# ir_receiver.net
KiCad netlist of a schematic drawn in EAGLE
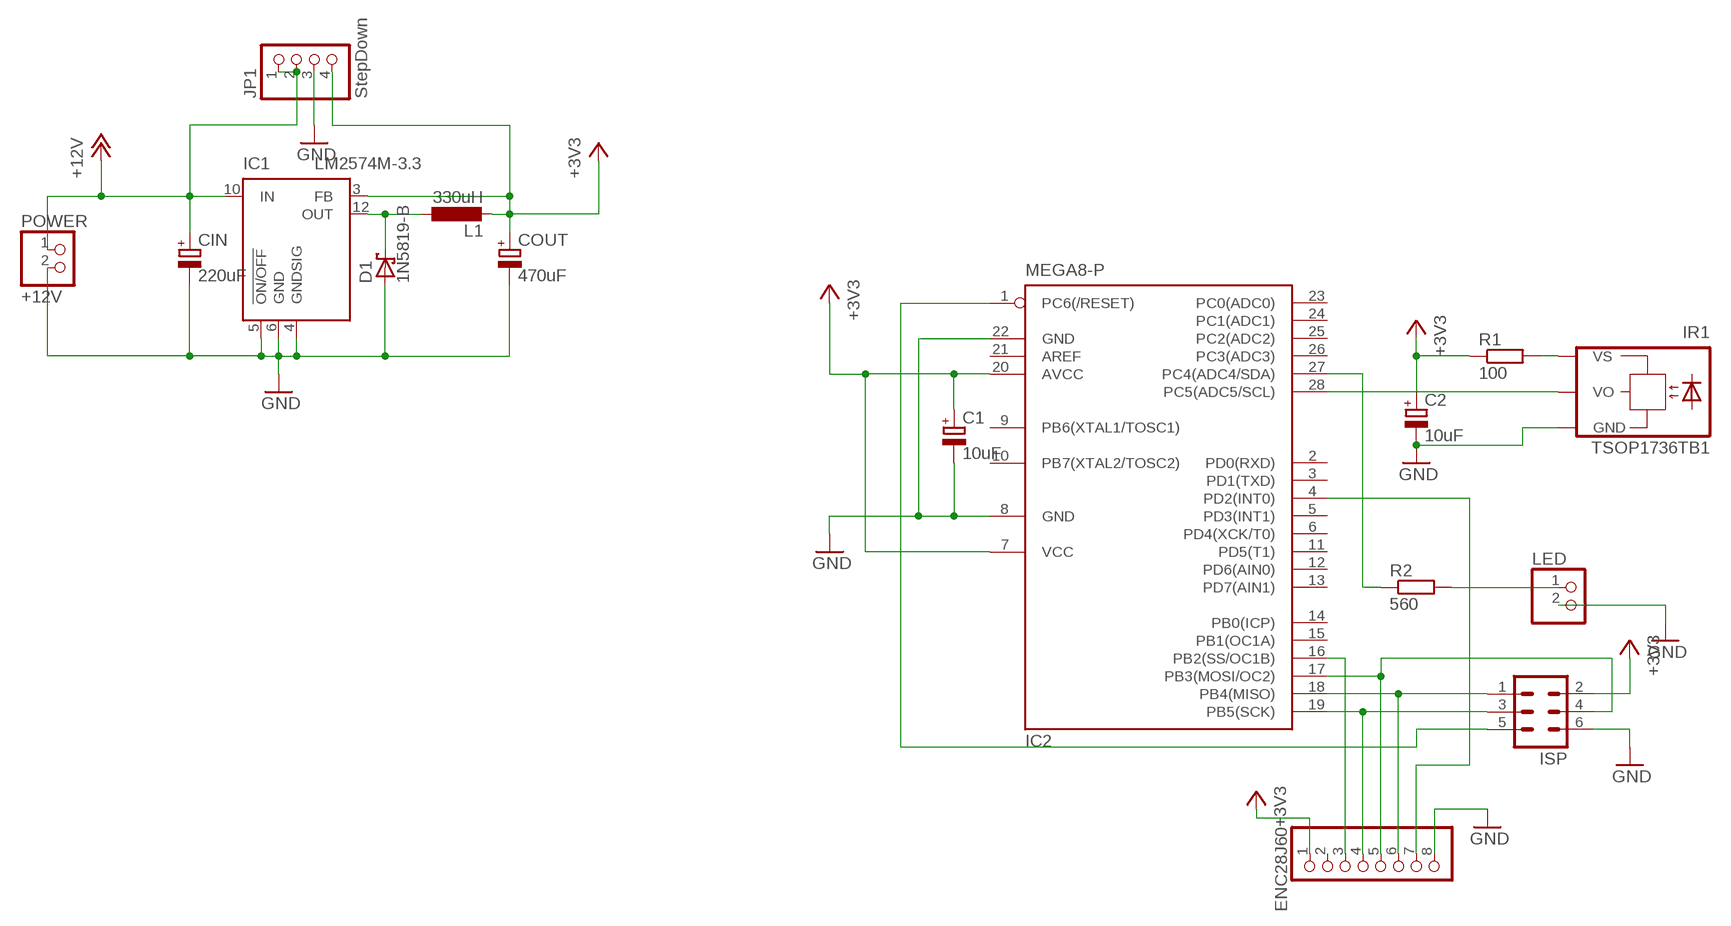
[diagram p0: schematic, sheet 1]

(export (version "E")
  (design (tool "Eeschema 10.0.6"))
  (components
    (comp (ref "C1")
      (value "10uF")
      (footprint "eagle-import:E2,5-5")
      (libsource (lib "eagle-import") (part "CPOL-EUE2.5-5"))
    )
    (comp (ref "C2")
      (value "10uF")
      (footprint "eagle-import:E2,5-5")
      (libsource (lib "eagle-import") (part "CPOL-EUE2.5-5"))
    )
    (comp (ref "CIN")
      (value "220uF")
      (footprint "eagle-import:E3,5-8")
      (libsource (lib "eagle-import") (part "CPOL-EUE3.5-8"))
    )
    (comp (ref "COUT")
      (value "470uF")
      (footprint "eagle-import:E5-10,5")
      (libsource (lib "eagle-import") (part "CPOL-EUE5-10.5"))
    )
    (comp (ref "D1")
      (value "1N5819-B")
      (footprint "eagle-import:DO41-7.6")
      (libsource (lib "eagle-import") (part "1N5819-B"))
    )
    (comp (ref "ENC28J60")
      (value "PINHD-1X8")
      (footprint "eagle-import:1X08")
      (libsource (lib "eagle-import") (part "PINHD-1X8"))
    )
    (comp (ref "IC1")
      (value "LM2574M-3.3")
      (footprint "eagle-import:SO14W")
      (libsource (lib "eagle-import") (part "LM2574?-M3.3"))
    )
    (comp (ref "IC2")
      (value "MEGA8-P")
      (footprint "eagle-import:DIL28-3")
      (libsource (lib "eagle-import") (part "MEGA8-P"))
    )
    (comp (ref "IR1")
      (value "TSOP1736TB1")
      (footprint "eagle-import:TSOP17_TB1")
      (libsource (lib "eagle-import") (part "TSOP17TB136"))
    )
    (comp (ref "ISP")
      (value "ML6")
      (footprint "eagle-import:ML6")
      (libsource (lib "eagle-import") (part "ML6"))
    )
    (comp (ref "JP1")
      (value "StepDown")
      (footprint "eagle-import:1X04")
      (libsource (lib "eagle-import") (part "PINHD-1X4"))
    )
    (comp (ref "L1")
      (value "330uH")
      (footprint "eagle-import:PIS2816")
      (libsource (lib "eagle-import") (part "PIS4728"))
    )
    (comp (ref "LED")
      (value "PINHD-1X2")
      (footprint "eagle-import:1X02")
      (libsource (lib "eagle-import") (part "PINHD-1X2"))
    )
    (comp (ref "POWER")
      (value "+12V")
      (footprint "eagle-import:1X02")
      (libsource (lib "eagle-import") (part "PINHD-1X2"))
    )
    (comp (ref "R1")
      (value "100")
      (footprint "eagle-import:0207_7")
      (libsource (lib "eagle-import") (part "R-EU_0207/7"))
    )
    (comp (ref "R2")
      (value "560")
      (footprint "eagle-import:0207_7")
      (libsource (lib "eagle-import") (part "R-EU_0207/7"))
    )
  )
  (nets
    (net (code "1") (name "+3V3") (class "Default")
      (node (ref "C1") (pin "+") (pinfunction "+_+") (pintype "passive"))
      (node (ref "C2") (pin "+") (pinfunction "+_+") (pintype "passive"))
      (node (ref "COUT") (pin "+") (pinfunction "+_+") (pintype "passive"))
      (node (ref "ENC28J60") (pin "1") (pinfunction "1_1") (pintype "passive"))
      (node (ref "IC1") (pin "3") (pinfunction "FB_3") (pintype "input"))
      (node (ref "IC2") (pin "20") (pinfunction "AVCC_20") (pintype "power_in"))
      (node (ref "IC2") (pin "7") (pinfunction "VCC_7") (pintype "power_in"))
      (node (ref "ISP") (pin "2") (pinfunction "2_2") (pintype "passive"))
      (node (ref "JP1") (pin "4") (pinfunction "4_4") (pintype "passive"))
      (node (ref "L1") (pin "2") (pinfunction "2_2") (pintype "passive"))
      (node (ref "R1") (pin "1") (pinfunction "1_1") (pintype "passive"))
    )
    (net (code "2") (name "+12V") (class "Default")
      (node (ref "CIN") (pin "+") (pinfunction "+_+") (pintype "passive"))
      (node (ref "IC1") (pin "10") (pinfunction "IN_10") (pintype "input"))
      (node (ref "JP1") (pin "1") (pinfunction "1_1") (pintype "passive"))
      (node (ref "JP1") (pin "2") (pinfunction "2_2") (pintype "passive"))
      (node (ref "POWER") (pin "1") (pinfunction "1_1") (pintype "passive"))
    )
    (net (code "3") (name "GND") (class "Default")
      (node (ref "C1") (pin "-") (pinfunction "-_-") (pintype "passive"))
      (node (ref "C2") (pin "-") (pinfunction "-_-") (pintype "passive"))
      (node (ref "CIN") (pin "-") (pinfunction "-_-") (pintype "passive"))
      (node (ref "COUT") (pin "-") (pinfunction "-_-") (pintype "passive"))
      (node (ref "D1") (pin "A") (pinfunction "A_A") (pintype "passive"))
      (node (ref "ENC28J60") (pin "8") (pinfunction "8_8") (pintype "passive"))
      (node (ref "IC1") (pin "4") (pinfunction "GNDSIG_4") (pintype "input"))
      (node (ref "IC1") (pin "5") (pinfunction "~{ON/OFF}_5") (pintype "input"))
      (node (ref "IC1") (pin "6") (pinfunction "GND_6") (pintype "power_in"))
      (node (ref "IC2") (pin "22") (pinfunction "GND_22") (pintype "power_in"))
      (node (ref "IC2") (pin "8") (pinfunction "GND_8") (pintype "power_in"))
      (node (ref "IR1") (pin "GND") (pinfunction "GND_GND") (pintype "power_in"))
      (node (ref "ISP") (pin "6") (pinfunction "6_6") (pintype "passive"))
      (node (ref "JP1") (pin "3") (pinfunction "3_3") (pintype "passive"))
      (node (ref "LED") (pin "2") (pinfunction "2_2") (pintype "passive"))
      (node (ref "POWER") (pin "2") (pinfunction "2_2") (pintype "passive"))
    )
    (net (code "4") (name "Net-(IC1-OUT)") (class "Default")
      (node (ref "D1") (pin "C") (pinfunction "C_C") (pintype "passive"))
      (node (ref "IC1") (pin "12") (pinfunction "OUT_12") (pintype "passive"))
      (node (ref "L1") (pin "1") (pinfunction "1_1") (pintype "passive"))
    )
    (net (code "5") (name "Net-(IC2-PB2(SS{slash}OC1B))") (class "Default")
      (node (ref "ENC28J60") (pin "3") (pinfunction "3_3") (pintype "passive"))
      (node (ref "IC2") (pin "16") (pinfunction "PB2(SS/OC1B)_16") (pintype "bidirectional"))
    )
    (net (code "6") (name "Net-(IC2-PB3(MOSI{slash}OC2))") (class "Default")
      (node (ref "ENC28J60") (pin "5") (pinfunction "5_5") (pintype "passive"))
      (node (ref "IC2") (pin "17") (pinfunction "PB3(MOSI/OC2)_17") (pintype "bidirectional"))
      (node (ref "ISP") (pin "4") (pinfunction "4_4") (pintype "passive"))
    )
    (net (code "7") (name "Net-(IC2-PB4(MISO))") (class "Default")
      (node (ref "ENC28J60") (pin "6") (pinfunction "6_6") (pintype "passive"))
      (node (ref "IC2") (pin "18") (pinfunction "PB4(MISO)_18") (pintype "bidirectional"))
      (node (ref "ISP") (pin "1") (pinfunction "1_1") (pintype "passive"))
    )
    (net (code "8") (name "Net-(IC2-PB5(SCK))") (class "Default")
      (node (ref "ENC28J60") (pin "4") (pinfunction "4_4") (pintype "passive"))
      (node (ref "IC2") (pin "19") (pinfunction "PB5(SCK)_19") (pintype "bidirectional"))
      (node (ref "ISP") (pin "3") (pinfunction "3_3") (pintype "passive"))
    )
    (net (code "9") (name "Net-(IC2-PC4(ADC4{slash}SDA))") (class "Default")
      (node (ref "IC2") (pin "27") (pinfunction "PC4(ADC4/SDA)_27") (pintype "bidirectional"))
      (node (ref "R2") (pin "1") (pinfunction "1_1") (pintype "passive"))
    )
    (net (code "10") (name "Net-(IC2-PC5(ADC5{slash}SCL))") (class "Default")
      (node (ref "IC2") (pin "28") (pinfunction "PC5(ADC5/SCL)_28") (pintype "bidirectional"))
      (node (ref "IR1") (pin "VO") (pinfunction "VO_VO") (pintype "open_collector"))
    )
    (net (code "11") (name "Net-(IC2-PC6({slash}RESET))") (class "Default")
      (node (ref "IC2") (pin "1") (pinfunction "PC6(/RESET)_1") (pintype "bidirectional"))
      (node (ref "ISP") (pin "5") (pinfunction "5_5") (pintype "passive"))
    )
    (net (code "12") (name "Net-(IC2-PD2(INT0))") (class "Default")
      (node (ref "ENC28J60") (pin "7") (pinfunction "7_7") (pintype "passive"))
      (node (ref "IC2") (pin "4") (pinfunction "PD2(INT0)_4") (pintype "bidirectional"))
    )
    (net (code "13") (name "Net-(IR1-PadVS)") (class "Default")
      (node (ref "IR1") (pin "VS") (pinfunction "VS_VS") (pintype "power_in"))
      (node (ref "R1") (pin "2") (pinfunction "2_2") (pintype "passive"))
    )
    (net (code "14") (name "Net-(LED-Pad1)") (class "Default")
      (node (ref "LED") (pin "1") (pinfunction "1_1") (pintype "passive"))
      (node (ref "R2") (pin "2") (pinfunction "2_2") (pintype "passive"))
    )
    (net (code "15") (name "unconnected-(ENC28J60-Pad2)") (class "Default")
      (node (ref "ENC28J60") (pin "2") (pinfunction "2_2") (pintype "passive"))
    )
    (net (code "16") (name "unconnected-(IC2-AREF-Pad21)") (class "Default")
      (node (ref "IC2") (pin "21") (pinfunction "AREF_21") (pintype "passive"))
    )
    (net (code "17") (name "unconnected-(IC2-PB0(ICP)-Pad14)") (class "Default")
      (node (ref "IC2") (pin "14") (pinfunction "PB0(ICP)_14") (pintype "bidirectional"))
    )
    (net (code "18") (name "unconnected-(IC2-PB1(OC1A)-Pad15)") (class "Default")
      (node (ref "IC2") (pin "15") (pinfunction "PB1(OC1A)_15") (pintype "bidirectional"))
    )
    (net (code "19") (name "unconnected-(IC2-PB6(XTAL1{slash}TOSC1)-Pad9)") (class "Default")
      (node (ref "IC2") (pin "9") (pinfunction "PB6(XTAL1/TOSC1)_9") (pintype "bidirectional"))
    )
    (net (code "20") (name "unconnected-(IC2-PB7(XTAL2{slash}TOSC2)-Pad10)") (class "Default")
      (node (ref "IC2") (pin "10") (pinfunction "PB7(XTAL2/TOSC2)_10") (pintype "bidirectional"))
    )
    (net (code "21") (name "unconnected-(IC2-PC0(ADC0)-Pad23)") (class "Default")
      (node (ref "IC2") (pin "23") (pinfunction "PC0(ADC0)_23") (pintype "bidirectional"))
    )
    (net (code "22") (name "unconnected-(IC2-PC1(ADC1)-Pad24)") (class "Default")
      (node (ref "IC2") (pin "24") (pinfunction "PC1(ADC1)_24") (pintype "bidirectional"))
    )
    (net (code "23") (name "unconnected-(IC2-PC2(ADC2)-Pad25)") (class "Default")
      (node (ref "IC2") (pin "25") (pinfunction "PC2(ADC2)_25") (pintype "bidirectional"))
    )
    (net (code "24") (name "unconnected-(IC2-PC3(ADC3)-Pad26)") (class "Default")
      (node (ref "IC2") (pin "26") (pinfunction "PC3(ADC3)_26") (pintype "bidirectional"))
    )
    (net (code "25") (name "unconnected-(IC2-PD0(RXD)-Pad2)") (class "Default")
      (node (ref "IC2") (pin "2") (pinfunction "PD0(RXD)_2") (pintype "bidirectional"))
    )
    (net (code "26") (name "unconnected-(IC2-PD1(TXD)-Pad3)") (class "Default")
      (node (ref "IC2") (pin "3") (pinfunction "PD1(TXD)_3") (pintype "bidirectional"))
    )
    (net (code "27") (name "unconnected-(IC2-PD3(INT1)-Pad5)") (class "Default")
      (node (ref "IC2") (pin "5") (pinfunction "PD3(INT1)_5") (pintype "bidirectional"))
    )
    (net (code "28") (name "unconnected-(IC2-PD4(XCK{slash}T0)-Pad6)") (class "Default")
      (node (ref "IC2") (pin "6") (pinfunction "PD4(XCK/T0)_6") (pintype "bidirectional"))
    )
    (net (code "29") (name "unconnected-(IC2-PD5(T1)-Pad11)") (class "Default")
      (node (ref "IC2") (pin "11") (pinfunction "PD5(T1)_11") (pintype "bidirectional"))
    )
    (net (code "30") (name "unconnected-(IC2-PD6(AIN0)-Pad12)") (class "Default")
      (node (ref "IC2") (pin "12") (pinfunction "PD6(AIN0)_12") (pintype "bidirectional"))
    )
    (net (code "31") (name "unconnected-(IC2-PD7(AIN1)-Pad13)") (class "Default")
      (node (ref "IC2") (pin "13") (pinfunction "PD7(AIN1)_13") (pintype "bidirectional"))
    )
  )
)
